# 6809_EXPANDED_V2_SBC.net
KiCad netlist of a schematic drawn in EAGLE
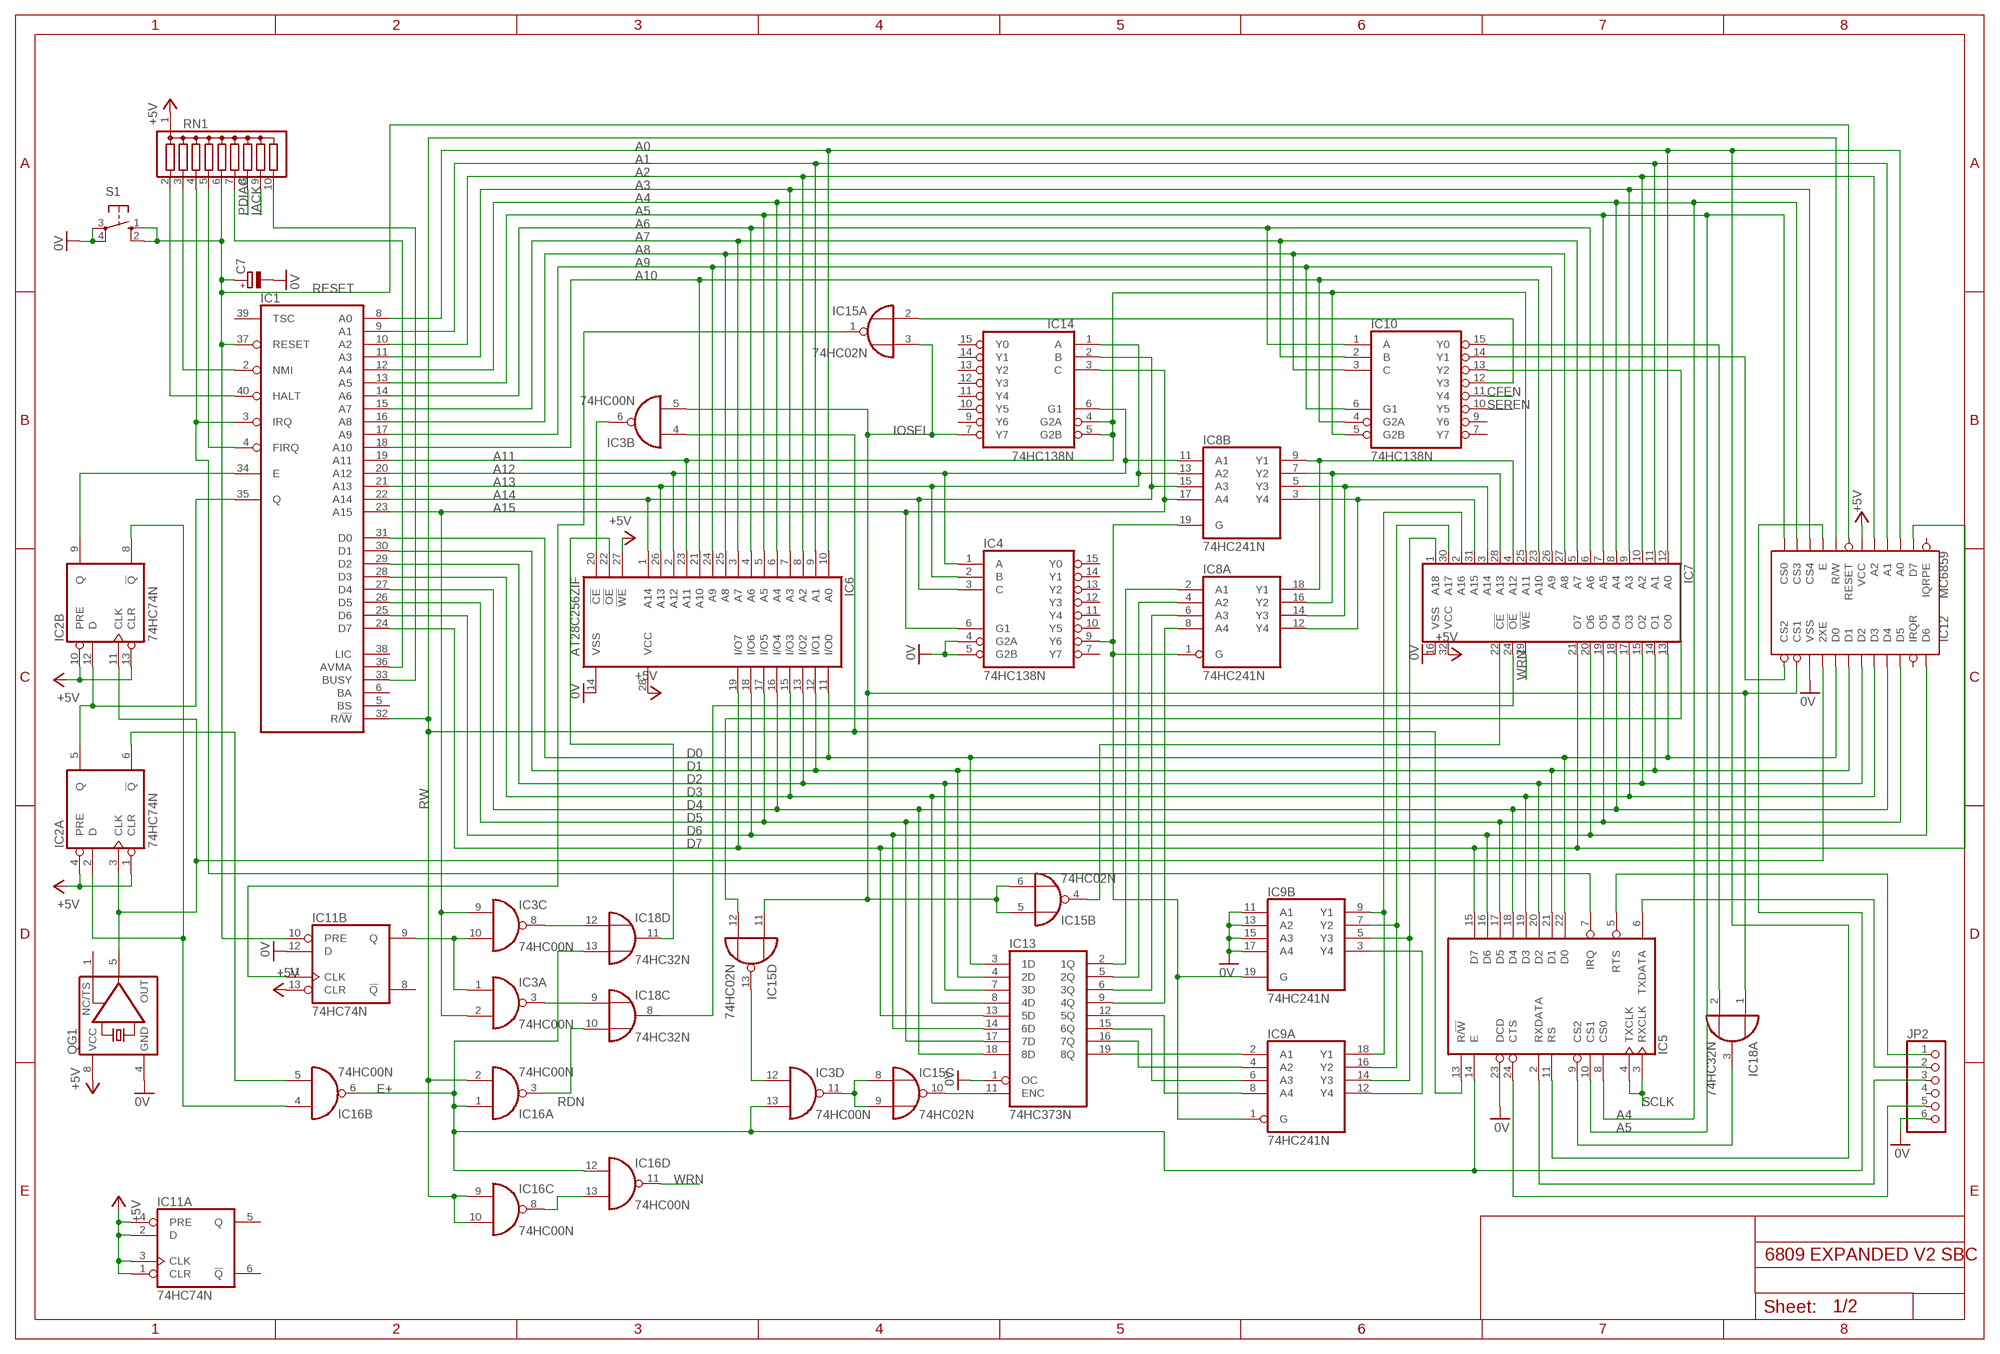
[diagram p0: schematic, sheet 1]
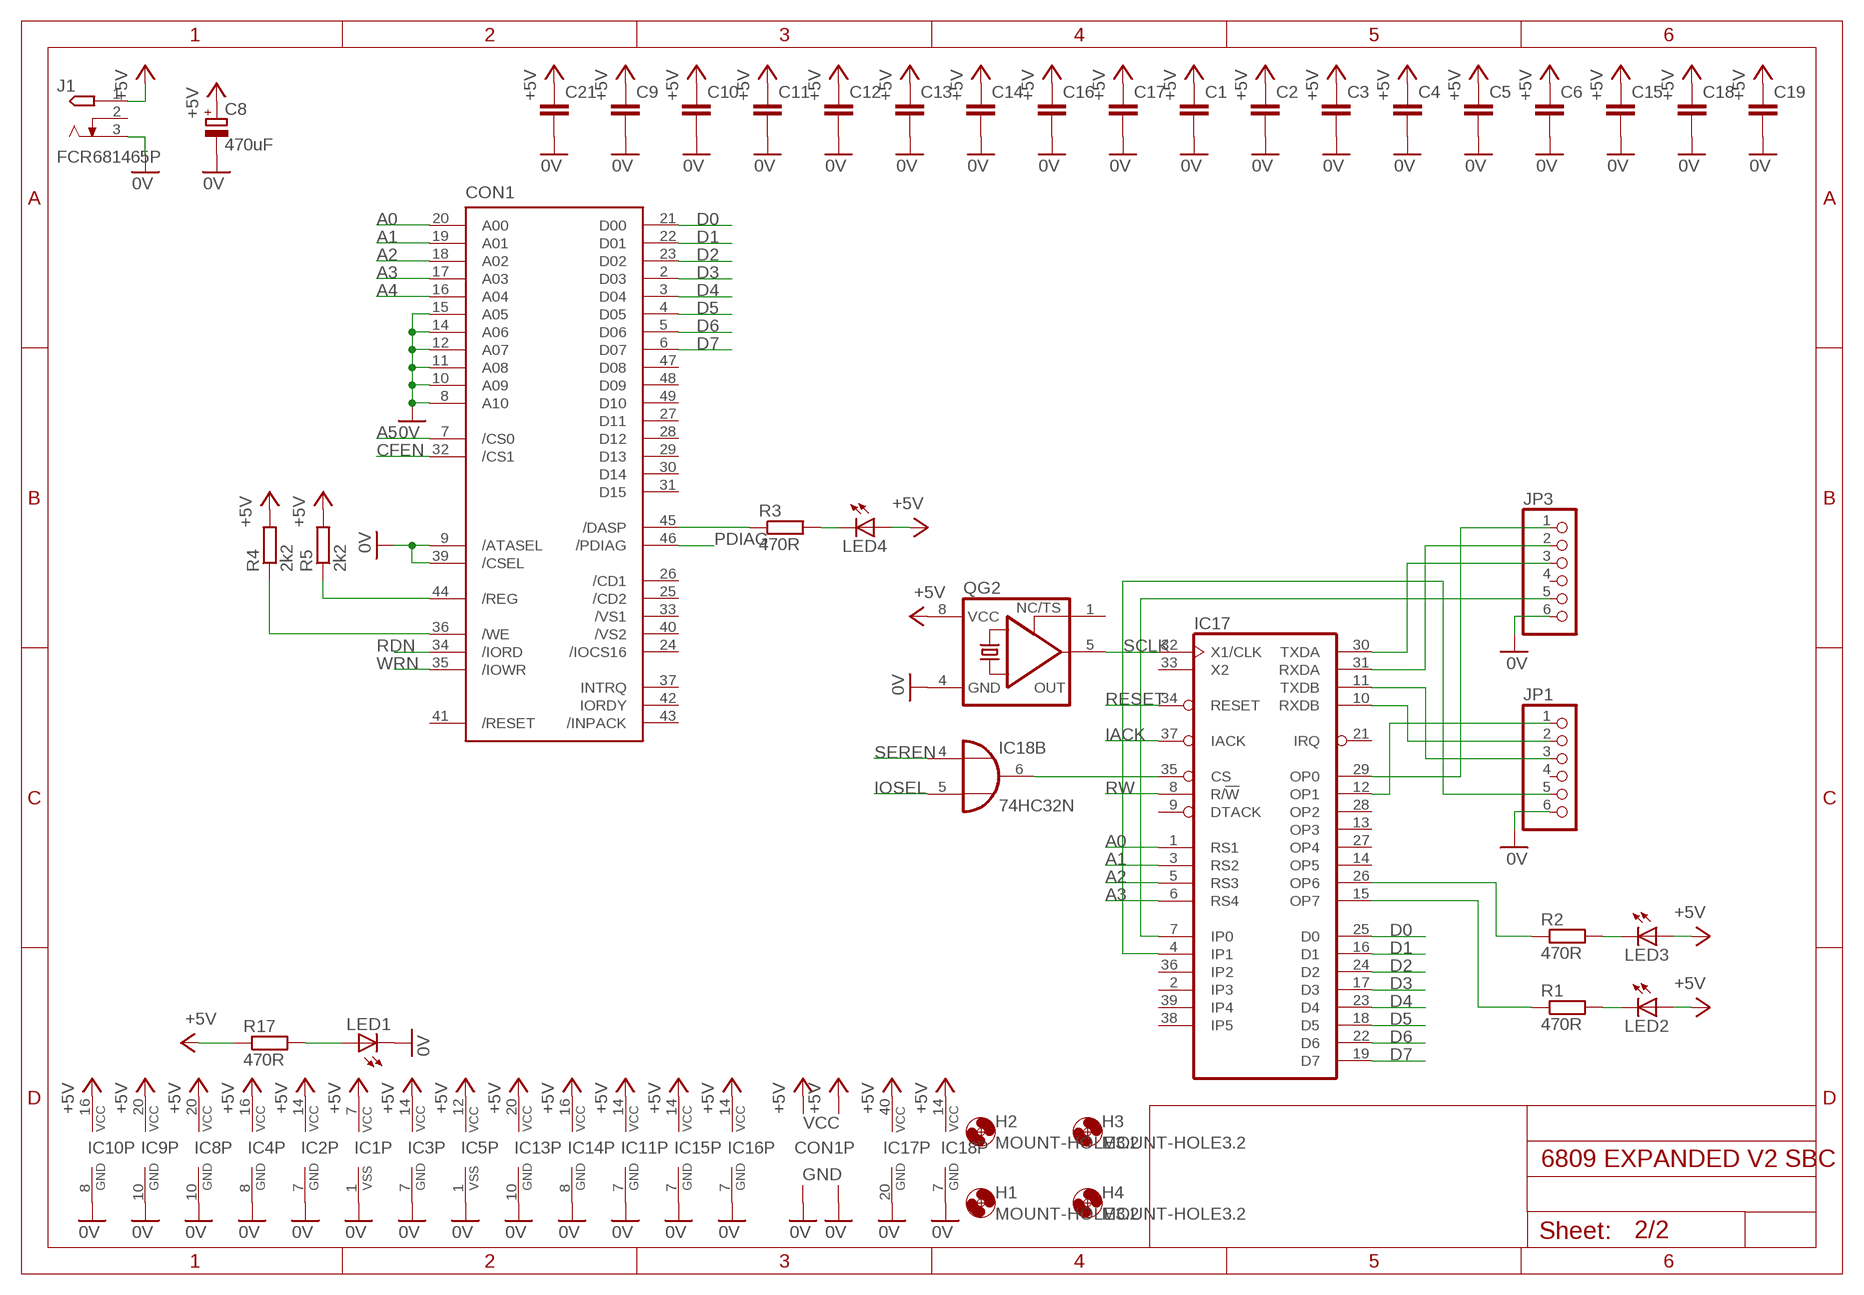
[diagram p1: schematic, sheet 2]

(export (version "E")
  (design (tool "Eeschema 10.0.6"))
  (components
    (comp (ref "C7")
      (value "CPOL-EUE2-5")
      (footprint "eagle-import:E2-5")
      (libsource (lib "eagle-import") (part "CPOL-EUE2-5"))
    )
    (comp (ref "IC1")
      (value "6809E")
      (footprint "eagle-import:DIL40")
      (fields (field (name "MF") "NTE ELECTRONICS") (field (name "MPN") "NTE6809E"))
      (libsource (lib "eagle-import") (part "6809E"))
    )
    (comp (ref "IC2")
      (value "74HC74N")
      (footprint "eagle-import:DIL14")
      (libsource (lib "eagle-import") (part "7474NHC"))
    )
    (comp (ref "IC3")
      (value "74HC00N")
      (footprint "eagle-import:DIL14")
      (libsource (lib "eagle-import") (part "7400NHC"))
    )
    (comp (ref "IC4")
      (value "74HC138N")
      (footprint "eagle-import:DIL16")
      (libsource (lib "eagle-import") (part "74138NHC"))
    )
    (comp (ref "IC5")
      (value "6850")
      (footprint "eagle-import:DIL24")
      (fields (field (name "MF") "NTE ELECTRONICS") (field (name "MPN") "NTE6850"))
      (libsource (lib "eagle-import") (part "6850"))
    )
    (comp (ref "IC6")
      (value "AT28C256ZIF")
      (footprint "eagle-import:228-1277-00-0602J")
      (libsource (lib "eagle-import") (part "AT28C256ZIF"))
    )
    (comp (ref "IC7")
      (value "AS6C4008")
      (footprint "eagle-import:DIL32")
      (libsource (lib "eagle-import") (part "AS6C4008"))
    )
    (comp (ref "IC8")
      (value "74HC241N")
      (footprint "eagle-import:DIL20")
      (libsource (lib "eagle-import") (part "74241NHC"))
    )
    (comp (ref "IC9")
      (value "74HC241N")
      (footprint "eagle-import:DIL20")
      (libsource (lib "eagle-import") (part "74241NHC"))
    )
    (comp (ref "IC10")
      (value "74HC138N")
      (footprint "eagle-import:DIL16")
      (libsource (lib "eagle-import") (part "74138NHC"))
    )
    (comp (ref "IC11")
      (value "74HC74N")
      (footprint "eagle-import:DIL14")
      (libsource (lib "eagle-import") (part "7474NHC"))
    )
    (comp (ref "IC12")
      (value "MC6859")
      (footprint "eagle-import:DIL24-6")
      (libsource (lib "eagle-import") (part "MC6859"))
    )
    (comp (ref "IC13")
      (value "74HC373N")
      (footprint "eagle-import:DIL20")
      (libsource (lib "eagle-import") (part "74373NHC"))
    )
    (comp (ref "IC14")
      (value "74HC138N")
      (footprint "eagle-import:DIL16")
      (libsource (lib "eagle-import") (part "74138NHC"))
    )
    (comp (ref "IC15")
      (value "74HC02N")
      (footprint "eagle-import:DIL14")
      (libsource (lib "eagle-import") (part "7402NHC"))
    )
    (comp (ref "IC16")
      (value "74HC00N")
      (footprint "eagle-import:DIL14")
      (libsource (lib "eagle-import") (part "7400NHC"))
    )
    (comp (ref "IC18")
      (value "74HC32N")
      (footprint "eagle-import:DIL14")
      (libsource (lib "eagle-import") (part "7432NHC"))
    )
    (comp (ref "JP2")
      (value "PINHD-1X6/90")
      (footprint "eagle-import:1X06_90")
      (libsource (lib "eagle-import") (part "PINHD-1X6/90"))
    )
    (comp (ref "QG1")
      (value "XO-8")
      (footprint "eagle-import:DIL08S")
      (libsource (lib "eagle-import") (part "XO-8"))
    )
    (comp (ref "RN1")
      (value "G09R")
      (footprint "eagle-import:SIL10")
      (libsource (lib "eagle-import") (part "G09R"))
    )
    (comp (ref "S1")
      (value "10-XX")
      (footprint "eagle-import:B3F-10XX")
      (fields (field (name "MPN") "B3F-1000"))
      (libsource (lib "eagle-import") (part "10-XX"))
    )
    (comp (ref "C1")
      (value "C-EU025-025X050")
      (footprint "eagle-import:C025-025X050")
      (libsource (lib "eagle-import") (part "C-EU025-025X050"))
    )
    (comp (ref "C2")
      (value "C-EU025-025X050")
      (footprint "eagle-import:C025-025X050")
      (libsource (lib "eagle-import") (part "C-EU025-025X050"))
    )
    (comp (ref "C3")
      (value "C-EU025-025X050")
      (footprint "eagle-import:C025-025X050")
      (libsource (lib "eagle-import") (part "C-EU025-025X050"))
    )
    (comp (ref "C4")
      (value "C-EU025-025X050")
      (footprint "eagle-import:C025-025X050")
      (libsource (lib "eagle-import") (part "C-EU025-025X050"))
    )
    (comp (ref "C5")
      (value "C-EU025-025X050")
      (footprint "eagle-import:C025-025X050")
      (libsource (lib "eagle-import") (part "C-EU025-025X050"))
    )
    (comp (ref "C6")
      (value "C-EU025-025X050")
      (footprint "eagle-import:C025-025X050")
      (libsource (lib "eagle-import") (part "C-EU025-025X050"))
    )
    (comp (ref "C8")
      (value "470uF")
      (footprint "eagle-import:E5-10,5")
      (libsource (lib "eagle-import") (part "CPOL-EUE5-10.5"))
    )
    (comp (ref "C9")
      (value "C-EU025-025X050")
      (footprint "eagle-import:C025-025X050")
      (libsource (lib "eagle-import") (part "C-EU025-025X050"))
    )
    (comp (ref "C10")
      (value "C-EU025-025X050")
      (footprint "eagle-import:C025-025X050")
      (libsource (lib "eagle-import") (part "C-EU025-025X050"))
    )
    (comp (ref "C11")
      (value "C-EU025-025X050")
      (footprint "eagle-import:C025-025X050")
      (libsource (lib "eagle-import") (part "C-EU025-025X050"))
    )
    (comp (ref "C12")
      (value "C-EU025-025X050")
      (footprint "eagle-import:C025-025X050")
      (libsource (lib "eagle-import") (part "C-EU025-025X050"))
    )
    (comp (ref "C13")
      (value "C-EU025-025X050")
      (footprint "eagle-import:C025-025X050")
      (libsource (lib "eagle-import") (part "C-EU025-025X050"))
    )
    (comp (ref "C14")
      (value "C-EU025-025X050")
      (footprint "eagle-import:C025-025X050")
      (libsource (lib "eagle-import") (part "C-EU025-025X050"))
    )
    (comp (ref "C15")
      (value "C-EU025-025X050")
      (footprint "eagle-import:C025-025X050")
      (libsource (lib "eagle-import") (part "C-EU025-025X050"))
    )
    (comp (ref "C16")
      (value "C-EU025-025X050")
      (footprint "eagle-import:C025-025X050")
      (libsource (lib "eagle-import") (part "C-EU025-025X050"))
    )
    (comp (ref "C17")
      (value "C-EU025-025X050")
      (footprint "eagle-import:C025-025X050")
      (libsource (lib "eagle-import") (part "C-EU025-025X050"))
    )
    (comp (ref "C18")
      (value "C-EU025-025X050")
      (footprint "eagle-import:C025-025X050")
      (libsource (lib "eagle-import") (part "C-EU025-025X050"))
    )
    (comp (ref "C19")
      (value "C-EU025-025X050")
      (footprint "eagle-import:C025-025X050")
      (libsource (lib "eagle-import") (part "C-EU025-025X050"))
    )
    (comp (ref "C21")
      (value "C-EU025-025X050")
      (footprint "eagle-import:C025-025X050")
      (libsource (lib "eagle-import") (part "C-EU025-025X050"))
    )
    (comp (ref "CON1")
      (value "CF-CARD-IDE_MODE")
      (footprint "eagle-import:MI20-50PD-SF")
      (libsource (lib "eagle-import") (part "CF-CARD-IDE_MODE"))
    )
    (comp (ref "H1")
      (value "MOUNT-HOLE3.2")
      (footprint "eagle-import:3,2")
      (libsource (lib "eagle-import") (part "MOUNT-HOLE3.2"))
    )
    (comp (ref "H2")
      (value "MOUNT-HOLE3.2")
      (footprint "eagle-import:3,2")
      (libsource (lib "eagle-import") (part "MOUNT-HOLE3.2"))
    )
    (comp (ref "H3")
      (value "MOUNT-HOLE3.2")
      (footprint "eagle-import:3,2")
      (libsource (lib "eagle-import") (part "MOUNT-HOLE3.2"))
    )
    (comp (ref "H4")
      (value "MOUNT-HOLE3.2")
      (footprint "eagle-import:3,2")
      (libsource (lib "eagle-import") (part "MOUNT-HOLE3.2"))
    )
    (comp (ref "IC17")
      (value "MC68681P")
      (footprint "eagle-import:DIL40")
      (libsource (lib "eagle-import") (part "MC68681P"))
    )
    (comp (ref "J1")
      (value "FCR681465P")
      (footprint "eagle-import:FCR681465P")
      (libsource (lib "eagle-import") (part "FCR681465P"))
    )
    (comp (ref "JP1")
      (value "PINHD-1X6/90")
      (footprint "eagle-import:1X06_90")
      (libsource (lib "eagle-import") (part "PINHD-1X6/90"))
    )
    (comp (ref "JP3")
      (value "PINHD-1X6/90")
      (footprint "eagle-import:1X06_90")
      (libsource (lib "eagle-import") (part "PINHD-1X6/90"))
    )
    (comp (ref "LED1")
      (value "LED3MM")
      (footprint "eagle-import:LED3MM")
      (libsource (lib "eagle-import") (part "LED3MM"))
    )
    (comp (ref "LED2")
      (value "LED3MM")
      (footprint "eagle-import:LED3MM")
      (libsource (lib "eagle-import") (part "LED3MM"))
    )
    (comp (ref "LED3")
      (value "LED3MM")
      (footprint "eagle-import:LED3MM")
      (libsource (lib "eagle-import") (part "LED3MM"))
    )
    (comp (ref "LED4")
      (value "LED3MM")
      (footprint "eagle-import:LED3MM")
      (libsource (lib "eagle-import") (part "LED3MM"))
    )
    (comp (ref "QG2")
      (value "XO-8")
      (footprint "eagle-import:DIL08S")
      (libsource (lib "eagle-import") (part "XO-8"))
    )
    (comp (ref "R1")
      (value "470R")
      (footprint "eagle-import:0207_10")
      (libsource (lib "eagle-import") (part "R-EU_0207/10"))
    )
    (comp (ref "R2")
      (value "470R")
      (footprint "eagle-import:0207_10")
      (libsource (lib "eagle-import") (part "R-EU_0207/10"))
    )
    (comp (ref "R3")
      (value "470R")
      (footprint "eagle-import:0207_10")
      (libsource (lib "eagle-import") (part "R-EU_0207/10"))
    )
    (comp (ref "R4")
      (value "2k2")
      (footprint "eagle-import:0207_10")
      (libsource (lib "eagle-import") (part "R-EU_0207/10"))
    )
    (comp (ref "R5")
      (value "2k2")
      (footprint "eagle-import:0207_10")
      (libsource (lib "eagle-import") (part "R-EU_0207/10"))
    )
    (comp (ref "R17")
      (value "470R")
      (footprint "eagle-import:0207_10")
      (libsource (lib "eagle-import") (part "R-EU_0207/10"))
    )
  )
  (nets
    (net (code "1") (name "+5V") (class "Default")
      (node (ref "C1") (pin "1") (pinfunction "1_1") (pintype "passive"))
      (node (ref "C10") (pin "1") (pinfunction "1_1") (pintype "passive"))
      (node (ref "C11") (pin "1") (pinfunction "1_1") (pintype "passive"))
      (node (ref "C12") (pin "1") (pinfunction "1_1") (pintype "passive"))
      (node (ref "C13") (pin "1") (pinfunction "1_1") (pintype "passive"))
      (node (ref "C14") (pin "1") (pinfunction "1_1") (pintype "passive"))
      (node (ref "C15") (pin "1") (pinfunction "1_1") (pintype "passive"))
      (node (ref "C16") (pin "1") (pinfunction "1_1") (pintype "passive"))
      (node (ref "C17") (pin "1") (pinfunction "1_1") (pintype "passive"))
      (node (ref "C18") (pin "1") (pinfunction "1_1") (pintype "passive"))
      (node (ref "C19") (pin "1") (pinfunction "1_1") (pintype "passive"))
      (node (ref "C2") (pin "1") (pinfunction "1_1") (pintype "passive"))
      (node (ref "C21") (pin "1") (pinfunction "1_1") (pintype "passive"))
      (node (ref "C3") (pin "1") (pinfunction "1_1") (pintype "passive"))
      (node (ref "C4") (pin "1") (pinfunction "1_1") (pintype "passive"))
      (node (ref "C5") (pin "1") (pinfunction "1_1") (pintype "passive"))
      (node (ref "C6") (pin "1") (pinfunction "1_1") (pintype "passive"))
      (node (ref "C8") (pin "+") (pinfunction "+_+") (pintype "passive"))
      (node (ref "C9") (pin "1") (pinfunction "1_1") (pintype "passive"))
      (node (ref "CON1") (pin "13") (pinfunction "VCC2_13") (pintype "power_in"))
      (node (ref "CON1") (pin "38") (pinfunction "VCC1_38") (pintype "power_in"))
      (node (ref "IC1") (pin "7") (pinfunction "VCC_7") (pintype "power_in"))
      (node (ref "IC10") (pin "16") (pinfunction "VCC_16") (pintype "power_in"))
      (node (ref "IC11") (pin "1") (pinfunction "CLR_1") (pintype "input"))
      (node (ref "IC11") (pin "13") (pinfunction "CLR_13") (pintype "input"))
      (node (ref "IC11") (pin "14") (pinfunction "VCC_14") (pintype "power_in"))
      (node (ref "IC11") (pin "2") (pinfunction "D_2") (pintype "input"))
      (node (ref "IC11") (pin "3") (pinfunction "CLK_3") (pintype "input"))
      (node (ref "IC11") (pin "4") (pinfunction "PRE_4") (pintype "input"))
      (node (ref "IC12") (pin "6") (pinfunction "VCC_6") (pintype "bidirectional"))
      (node (ref "IC13") (pin "20") (pinfunction "VCC_20") (pintype "power_in"))
      (node (ref "IC14") (pin "16") (pinfunction "VCC_16") (pintype "power_in"))
      (node (ref "IC15") (pin "14") (pinfunction "VCC_14") (pintype "power_in"))
      (node (ref "IC16") (pin "14") (pinfunction "VCC_14") (pintype "power_in"))
      (node (ref "IC17") (pin "40") (pinfunction "VCC_40") (pintype "power_in"))
      (node (ref "IC18") (pin "14") (pinfunction "VCC_14") (pintype "power_in"))
      (node (ref "IC2") (pin "1") (pinfunction "CLR_1") (pintype "input"))
      (node (ref "IC2") (pin "10") (pinfunction "PRE_10") (pintype "input"))
      (node (ref "IC2") (pin "13") (pinfunction "CLR_13") (pintype "input"))
      (node (ref "IC2") (pin "14") (pinfunction "VCC_14") (pintype "power_in"))
      (node (ref "IC2") (pin "4") (pinfunction "PRE_4") (pintype "input"))
      (node (ref "IC3") (pin "14") (pinfunction "VCC_14") (pintype "power_in"))
      (node (ref "IC4") (pin "16") (pinfunction "VCC_16") (pintype "power_in"))
      (node (ref "IC5") (pin "12") (pinfunction "VCC_12") (pintype "power_in"))
      (node (ref "IC6") (pin "27") (pinfunction "~{WE}_27") (pintype "input"))
      (node (ref "IC6") (pin "28") (pinfunction "VCC_28") (pintype "power_in"))
      (node (ref "IC7") (pin "32") (pinfunction "VCC_32") (pintype "tri_state"))
      (node (ref "IC8") (pin "20") (pinfunction "VCC_20") (pintype "power_in"))
      (node (ref "IC9") (pin "20") (pinfunction "VCC_20") (pintype "power_in"))
      (node (ref "J1") (pin "1") (pinfunction "1_1") (pintype "passive"))
      (node (ref "LED2") (pin "A") (pinfunction "A_A") (pintype "passive"))
      (node (ref "LED3") (pin "A") (pinfunction "A_A") (pintype "passive"))
      (node (ref "LED4") (pin "A") (pinfunction "A_A") (pintype "passive"))
      (node (ref "QG1") (pin "8") (pinfunction "VCC_8") (pintype "power_in"))
      (node (ref "QG2") (pin "8") (pinfunction "VCC_8") (pintype "power_in"))
      (node (ref "R17") (pin "1") (pinfunction "1_1") (pintype "passive"))
      (node (ref "R4") (pin "2") (pinfunction "2_2") (pintype "passive"))
      (node (ref "R5") (pin "2") (pinfunction "2_2") (pintype "passive"))
      (node (ref "RN1") (pin "1") (pinfunction "1_1") (pintype "passive"))
    )
    (net (code "2") (name "0V") (class "Default")
      (node (ref "C1") (pin "2") (pinfunction "2_2") (pintype "passive"))
      (node (ref "C10") (pin "2") (pinfunction "2_2") (pintype "passive"))
      (node (ref "C11") (pin "2") (pinfunction "2_2") (pintype "passive"))
      (node (ref "C12") (pin "2") (pinfunction "2_2") (pintype "passive"))
      (node (ref "C13") (pin "2") (pinfunction "2_2") (pintype "passive"))
      (node (ref "C14") (pin "2") (pinfunction "2_2") (pintype "passive"))
      (node (ref "C15") (pin "2") (pinfunction "2_2") (pintype "passive"))
      (node (ref "C16") (pin "2") (pinfunction "2_2") (pintype "passive"))
      (node (ref "C17") (pin "2") (pinfunction "2_2") (pintype "passive"))
      (node (ref "C18") (pin "2") (pinfunction "2_2") (pintype "passive"))
      (node (ref "C19") (pin "2") (pinfunction "2_2") (pintype "passive"))
      (node (ref "C2") (pin "2") (pinfunction "2_2") (pintype "passive"))
      (node (ref "C21") (pin "2") (pinfunction "2_2") (pintype "passive"))
      (node (ref "C3") (pin "2") (pinfunction "2_2") (pintype "passive"))
      (node (ref "C4") (pin "2") (pinfunction "2_2") (pintype "passive"))
      (node (ref "C5") (pin "2") (pinfunction "2_2") (pintype "passive"))
      (node (ref "C6") (pin "2") (pinfunction "2_2") (pintype "passive"))
      (node (ref "C7") (pin "-") (pinfunction "-_-") (pintype "passive"))
      (node (ref "C8") (pin "-") (pinfunction "-_-") (pintype "passive"))
      (node (ref "C9") (pin "2") (pinfunction "2_2") (pintype "passive"))
      (node (ref "CON1") (pin "1") (pinfunction "GND1_1") (pintype "power_in"))
      (node (ref "CON1") (pin "10") (pinfunction "A09_10") (pintype "input"))
      (node (ref "CON1") (pin "11") (pinfunction "A08_11") (pintype "input"))
      (node (ref "CON1") (pin "12") (pinfunction "A07_12") (pintype "input"))
      (node (ref "CON1") (pin "14") (pinfunction "A06_14") (pintype "input"))
      (node (ref "CON1") (pin "15") (pinfunction "A05_15") (pintype "input"))
      (node (ref "CON1") (pin "39") (pinfunction "/CSEL_39") (pintype "input"))
      (node (ref "CON1") (pin "50") (pinfunction "GND2_50") (pintype "power_in"))
      (node (ref "CON1") (pin "8") (pinfunction "A10_8") (pintype "input"))
      (node (ref "CON1") (pin "9") (pinfunction "/ATASEL_9") (pintype "input"))
      (node (ref "IC1") (pin "1") (pinfunction "VSS_1") (pintype "power_in"))
      (node (ref "IC10") (pin "8") (pinfunction "GND_8") (pintype "power_in"))
      (node (ref "IC11") (pin "12") (pinfunction "D_12") (pintype "input"))
      (node (ref "IC11") (pin "7") (pinfunction "GND_7") (pintype "power_in"))
      (node (ref "IC12") (pin "15") (pinfunction "VSS_15") (pintype "bidirectional"))
      (node (ref "IC13") (pin "1") (pinfunction "OC_1") (pintype "input"))
      (node (ref "IC13") (pin "10") (pinfunction "GND_10") (pintype "power_in"))
      (node (ref "IC14") (pin "8") (pinfunction "GND_8") (pintype "power_in"))
      (node (ref "IC15") (pin "7") (pinfunction "GND_7") (pintype "power_in"))
      (node (ref "IC16") (pin "7") (pinfunction "GND_7") (pintype "power_in"))
      (node (ref "IC17") (pin "20") (pinfunction "GND_20") (pintype "power_in"))
      (node (ref "IC18") (pin "7") (pinfunction "GND_7") (pintype "power_in"))
      (node (ref "IC2") (pin "7") (pinfunction "GND_7") (pintype "power_in"))
      (node (ref "IC3") (pin "7") (pinfunction "GND_7") (pintype "power_in"))
      (node (ref "IC4") (pin "4") (pinfunction "G2A_4") (pintype "input"))
      (node (ref "IC4") (pin "5") (pinfunction "G2B_5") (pintype "input"))
      (node (ref "IC4") (pin "8") (pinfunction "GND_8") (pintype "power_in"))
      (node (ref "IC5") (pin "1") (pinfunction "VSS_1") (pintype "power_in"))
      (node (ref "IC5") (pin "23") (pinfunction "DCD_23") (pintype "input"))
      (node (ref "IC6") (pin "14") (pinfunction "VSS_14") (pintype "power_in"))
      (node (ref "IC7") (pin "16") (pinfunction "VSS_16") (pintype "tri_state"))
      (node (ref "IC8") (pin "10") (pinfunction "GND_10") (pintype "power_in"))
      (node (ref "IC9") (pin "10") (pinfunction "GND_10") (pintype "power_in"))
      (node (ref "IC9") (pin "11") (pinfunction "A1_11") (pintype "input"))
      (node (ref "IC9") (pin "13") (pinfunction "A2_13") (pintype "input"))
      (node (ref "IC9") (pin "15") (pinfunction "A3_15") (pintype "input"))
      (node (ref "IC9") (pin "17") (pinfunction "A4_17") (pintype "input"))
      (node (ref "J1") (pin "3") (pinfunction "3_3") (pintype "passive"))
      (node (ref "JP1") (pin "6") (pinfunction "6_6") (pintype "passive"))
      (node (ref "JP2") (pin "6") (pinfunction "6_6") (pintype "passive"))
      (node (ref "JP3") (pin "6") (pinfunction "6_6") (pintype "passive"))
      (node (ref "LED1") (pin "K") (pinfunction "C_K") (pintype "passive"))
      (node (ref "QG1") (pin "4") (pinfunction "GND_4") (pintype "power_in"))
      (node (ref "QG2") (pin "4") (pinfunction "GND_4") (pintype "power_in"))
      (node (ref "S1") (pin "3") (pinfunction "P_3") (pintype "passive"))
      (node (ref "S1") (pin "4") (pinfunction "P1_4") (pintype "passive"))
    )
    (net (code "3") (name "A0") (class "Default")
      (node (ref "CON1") (pin "20") (pinfunction "A00_20") (pintype "input"))
      (node (ref "IC1") (pin "8") (pinfunction "A0_8") (pintype "tri_state"))
      (node (ref "IC12") (pin "3") (pinfunction "A0_3") (pintype "bidirectional"))
      (node (ref "IC17") (pin "1") (pinfunction "RS1_1") (pintype "input"))
      (node (ref "IC5") (pin "11") (pinfunction "RS_11") (pintype "input"))
      (node (ref "IC6") (pin "10") (pinfunction "A0_10") (pintype "input"))
      (node (ref "IC7") (pin "12") (pinfunction "A0_12") (pintype "input"))
    )
    (net (code "4") (name "A1") (class "Default")
      (node (ref "CON1") (pin "19") (pinfunction "A01_19") (pintype "input"))
      (node (ref "IC1") (pin "9") (pinfunction "A1_9") (pintype "tri_state"))
      (node (ref "IC12") (pin "4") (pinfunction "A1_4") (pintype "bidirectional"))
      (node (ref "IC17") (pin "3") (pinfunction "RS2_3") (pintype "input"))
      (node (ref "IC6") (pin "9") (pinfunction "A1_9") (pintype "input"))
      (node (ref "IC7") (pin "11") (pinfunction "A1_11") (pintype "input"))
    )
    (net (code "5") (name "A2") (class "Default")
      (node (ref "CON1") (pin "18") (pinfunction "A02_18") (pintype "input"))
      (node (ref "IC1") (pin "10") (pinfunction "A2_10") (pintype "tri_state"))
      (node (ref "IC12") (pin "5") (pinfunction "A2_5") (pintype "bidirectional"))
      (node (ref "IC17") (pin "5") (pinfunction "RS3_5") (pintype "input"))
      (node (ref "IC6") (pin "8") (pinfunction "A2_8") (pintype "input"))
      (node (ref "IC7") (pin "10") (pinfunction "A2_10") (pintype "input"))
    )
    (net (code "6") (name "A3") (class "Default")
      (node (ref "CON1") (pin "17") (pinfunction "A03_17") (pintype "input"))
      (node (ref "IC1") (pin "11") (pinfunction "A3_11") (pintype "tri_state"))
      (node (ref "IC12") (pin "10") (pinfunction "CS4_10") (pintype "bidirectional"))
      (node (ref "IC17") (pin "6") (pinfunction "RS4_6") (pintype "input"))
      (node (ref "IC6") (pin "7") (pinfunction "A3_7") (pintype "input"))
      (node (ref "IC7") (pin "9") (pinfunction "A3_9") (pintype "input"))
    )
    (net (code "7") (name "A4") (class "Default")
      (node (ref "CON1") (pin "16") (pinfunction "A04_16") (pintype "input"))
      (node (ref "IC1") (pin "12") (pinfunction "A4_12") (pintype "tri_state"))
      (node (ref "IC12") (pin "11") (pinfunction "CS3_11") (pintype "bidirectional"))
      (node (ref "IC5") (pin "8") (pinfunction "CS0_8") (pintype "input"))
      (node (ref "IC6") (pin "6") (pinfunction "A4_6") (pintype "input"))
      (node (ref "IC7") (pin "8") (pinfunction "A4_8") (pintype "input"))
    )
    (net (code "8") (name "A5") (class "Default")
      (node (ref "CON1") (pin "7") (pinfunction "/CS0_7") (pintype "input"))
      (node (ref "IC1") (pin "13") (pinfunction "A5_13") (pintype "tri_state"))
      (node (ref "IC12") (pin "12") (pinfunction "CS0_12") (pintype "bidirectional"))
      (node (ref "IC5") (pin "10") (pinfunction "CS1_10") (pintype "input"))
      (node (ref "IC6") (pin "5") (pinfunction "A5_5") (pintype "input"))
      (node (ref "IC7") (pin "7") (pinfunction "A5_7") (pintype "input"))
    )
    (net (code "9") (name "A6") (class "Default")
      (node (ref "IC1") (pin "14") (pinfunction "A6_14") (pintype "tri_state"))
      (node (ref "IC10") (pin "1") (pinfunction "A_1") (pintype "input"))
      (node (ref "IC6") (pin "4") (pinfunction "A6_4") (pintype "input"))
      (node (ref "IC7") (pin "6") (pinfunction "A6_6") (pintype "input"))
    )
    (net (code "10") (name "A7") (class "Default")
      (node (ref "IC1") (pin "15") (pinfunction "A7_15") (pintype "tri_state"))
      (node (ref "IC10") (pin "2") (pinfunction "B_2") (pintype "input"))
      (node (ref "IC6") (pin "3") (pinfunction "A7_3") (pintype "input"))
      (node (ref "IC7") (pin "5") (pinfunction "A7_5") (pintype "input"))
    )
    (net (code "11") (name "A8") (class "Default")
      (node (ref "IC1") (pin "16") (pinfunction "A8_16") (pintype "tri_state"))
      (node (ref "IC10") (pin "3") (pinfunction "C_3") (pintype "input"))
      (node (ref "IC6") (pin "25") (pinfunction "A8_25") (pintype "input"))
      (node (ref "IC7") (pin "27") (pinfunction "A8_27") (pintype "input"))
    )
    (net (code "12") (name "A9") (class "Default")
      (node (ref "IC1") (pin "17") (pinfunction "A9_17") (pintype "tri_state"))
      (node (ref "IC10") (pin "6") (pinfunction "G1_6") (pintype "input"))
      (node (ref "IC6") (pin "24") (pinfunction "A9_24") (pintype "input"))
      (node (ref "IC7") (pin "26") (pinfunction "A9_26") (pintype "input"))
    )
    (net (code "13") (name "A10") (class "Default")
      (node (ref "IC1") (pin "18") (pinfunction "A10_18") (pintype "tri_state"))
      (node (ref "IC10") (pin "4") (pinfunction "G2A_4") (pintype "input"))
      (node (ref "IC6") (pin "21") (pinfunction "A10_21") (pintype "input"))
      (node (ref "IC7") (pin "23") (pinfunction "A10_23") (pintype "input"))
    )
    (net (code "14") (name "A11") (class "Default")
      (node (ref "IC1") (pin "19") (pinfunction "A11_19") (pintype "tri_state"))
      (node (ref "IC10") (pin "5") (pinfunction "G2B_5") (pintype "input"))
      (node (ref "IC14") (pin "4") (pinfunction "G2A_4") (pintype "input"))
      (node (ref "IC14") (pin "5") (pinfunction "G2B_5") (pintype "input"))
      (node (ref "IC6") (pin "23") (pinfunction "A11_23") (pintype "input"))
      (node (ref "IC7") (pin "25") (pinfunction "A11_25") (pintype "input"))
    )
    (net (code "15") (name "A12") (class "Default")
      (node (ref "IC1") (pin "20") (pinfunction "A12_20") (pintype "tri_state"))
      (node (ref "IC14") (pin "6") (pinfunction "G1_6") (pintype "input"))
      (node (ref "IC4") (pin "1") (pinfunction "A_1") (pintype "input"))
      (node (ref "IC6") (pin "2") (pinfunction "A12_2") (pintype "input"))
      (node (ref "IC8") (pin "11") (pinfunction "A1_11") (pintype "input"))
    )
    (net (code "16") (name "A13") (class "Default")
      (node (ref "IC1") (pin "21") (pinfunction "A13_21") (pintype "tri_state"))
      (node (ref "IC14") (pin "1") (pinfunction "A_1") (pintype "input"))
      (node (ref "IC4") (pin "2") (pinfunction "B_2") (pintype "input"))
      (node (ref "IC6") (pin "26") (pinfunction "A13_26") (pintype "input"))
      (node (ref "IC8") (pin "13") (pinfunction "A2_13") (pintype "input"))
    )
    (net (code "17") (name "A14") (class "Default")
      (node (ref "IC1") (pin "22") (pinfunction "A14_22") (pintype "tri_state"))
      (node (ref "IC14") (pin "2") (pinfunction "B_2") (pintype "input"))
      (node (ref "IC4") (pin "3") (pinfunction "C_3") (pintype "input"))
      (node (ref "IC6") (pin "1") (pinfunction "A14_1") (pintype "input"))
      (node (ref "IC8") (pin "15") (pinfunction "A3_15") (pintype "input"))
    )
    (net (code "18") (name "A15") (class "Default")
      (node (ref "IC1") (pin "23") (pinfunction "A15_23") (pintype "tri_state"))
      (node (ref "IC14") (pin "3") (pinfunction "C_3") (pintype "input"))
      (node (ref "IC3") (pin "2") (pinfunction "I1_2") (pintype "input"))
      (node (ref "IC3") (pin "9") (pinfunction "I0_9") (pintype "input"))
      (node (ref "IC4") (pin "6") (pinfunction "G1_6") (pintype "input"))
      (node (ref "IC8") (pin "17") (pinfunction "A4_17") (pintype "input"))
    )
    (net (code "19") (name "CFEN") (class "Default")
      (node (ref "CON1") (pin "32") (pinfunction "/CS1_32") (pintype "input"))
      (node (ref "IC10") (pin "11") (pinfunction "Y4_11") (pintype "output"))
    )
    (net (code "20") (name "D0") (class "Default")
      (node (ref "CON1") (pin "21") (pinfunction "D00_21") (pintype "bidirectional"))
      (node (ref "IC1") (pin "31") (pinfunction "D0_31") (pintype "bidirectional"))
      (node (ref "IC12") (pin "17") (pinfunction "D0_17") (pintype "bidirectional"))
      (node (ref "IC13") (pin "3") (pinfunction "1D_3") (pintype "input"))
      (node (ref "IC17") (pin "25") (pinfunction "D0_25") (pintype "bidirectional"))
      (node (ref "IC5") (pin "22") (pinfunction "D0_22") (pintype "bidirectional"))
      (node (ref "IC6") (pin "11") (pinfunction "I/O0_11") (pintype "tri_state"))
      (node (ref "IC7") (pin "13") (pinfunction "O0_13") (pintype "tri_state"))
    )
    (net (code "21") (name "D1") (class "Default")
      (node (ref "CON1") (pin "22") (pinfunction "D01_22") (pintype "bidirectional"))
      (node (ref "IC1") (pin "30") (pinfunction "D1_30") (pintype "bidirectional"))
      (node (ref "IC12") (pin "18") (pinfunction "D1_18") (pintype "bidirectional"))
      (node (ref "IC13") (pin "4") (pinfunction "2D_4") (pintype "input"))
      (node (ref "IC17") (pin "16") (pinfunction "D1_16") (pintype "bidirectional"))
      (node (ref "IC5") (pin "21") (pinfunction "D1_21") (pintype "bidirectional"))
      (node (ref "IC6") (pin "12") (pinfunction "I/O1_12") (pintype "tri_state"))
      (node (ref "IC7") (pin "14") (pinfunction "O1_14") (pintype "tri_state"))
    )
    (net (code "22") (name "D2") (class "Default")
      (node (ref "CON1") (pin "23") (pinfunction "D02_23") (pintype "bidirectional"))
      (node (ref "IC1") (pin "29") (pinfunction "D2_29") (pintype "bidirectional"))
      (node (ref "IC12") (pin "19") (pinfunction "D2_19") (pintype "bidirectional"))
      (node (ref "IC13") (pin "7") (pinfunction "3D_7") (pintype "input"))
      (node (ref "IC17") (pin "24") (pinfunction "D2_24") (pintype "bidirectional"))
      (node (ref "IC5") (pin "20") (pinfunction "D2_20") (pintype "bidirectional"))
      (node (ref "IC6") (pin "13") (pinfunction "I/O2_13") (pintype "tri_state"))
      (node (ref "IC7") (pin "15") (pinfunction "O2_15") (pintype "tri_state"))
    )
    (net (code "23") (name "D3") (class "Default")
      (node (ref "CON1") (pin "2") (pinfunction "D03_2") (pintype "bidirectional"))
      (node (ref "IC1") (pin "28") (pinfunction "D3_28") (pintype "bidirectional"))
      (node (ref "IC12") (pin "20") (pinfunction "D3_20") (pintype "bidirectional"))
      (node (ref "IC13") (pin "8") (pinfunction "4D_8") (pintype "input"))
      (node (ref "IC17") (pin "17") (pinfunction "D3_17") (pintype "bidirectional"))
      (node (ref "IC5") (pin "19") (pinfunction "D3_19") (pintype "bidirectional"))
      (node (ref "IC6") (pin "15") (pinfunction "I/O3_15") (pintype "tri_state"))
      (node (ref "IC7") (pin "17") (pinfunction "O3_17") (pintype "tri_state"))
    )
    (net (code "24") (name "D4") (class "Default")
      (node (ref "CON1") (pin "3") (pinfunction "D04_3") (pintype "bidirectional"))
      (node (ref "IC1") (pin "27") (pinfunction "D4_27") (pintype "bidirectional"))
      (node (ref "IC12") (pin "21") (pinfunction "D4_21") (pintype "bidirectional"))
      (node (ref "IC13") (pin "18") (pinfunction "8D_18") (pintype "input"))
      (node (ref "IC17") (pin "23") (pinfunction "D4_23") (pintype "bidirectional"))
      (node (ref "IC5") (pin "18") (pinfunction "D4_18") (pintype "bidirectional"))
      (node (ref "IC6") (pin "16") (pinfunction "I/O4_16") (pintype "tri_state"))
      (node (ref "IC7") (pin "18") (pinfunction "O4_18") (pintype "tri_state"))
    )
    (net (code "25") (name "D5") (class "Default")
      (node (ref "CON1") (pin "4") (pinfunction "D05_4") (pintype "bidirectional"))
      (node (ref "IC1") (pin "26") (pinfunction "D5_26") (pintype "bidirectional"))
      (node (ref "IC12") (pin "22") (pinfunction "D5_22") (pintype "bidirectional"))
      (node (ref "IC13") (pin "17") (pinfunction "7D_17") (pintype "input"))
      (node (ref "IC17") (pin "18") (pinfunction "D5_18") (pintype "bidirectional"))
      (node (ref "IC5") (pin "17") (pinfunction "D5_17") (pintype "bidirectional"))
      (node (ref "IC6") (pin "17") (pinfunction "I/O5_17") (pintype "tri_state"))
      (node (ref "IC7") (pin "19") (pinfunction "O5_19") (pintype "tri_state"))
    )
    (net (code "26") (name "D6") (class "Default")
      (node (ref "CON1") (pin "5") (pinfunction "D06_5") (pintype "bidirectional"))
      (node (ref "IC1") (pin "25") (pinfunction "D6_25") (pintype "bidirectional"))
      (node (ref "IC12") (pin "24") (pinfunction "D6_24") (pintype "bidirectional"))
      (node (ref "IC13") (pin "14") (pinfunction "6D_14") (pintype "input"))
      (node (ref "IC17") (pin "22") (pinfunction "D6_22") (pintype "bidirectional"))
      (node (ref "IC5") (pin "16") (pinfunction "D6_16") (pintype "bidirectional"))
      (node (ref "IC6") (pin "18") (pinfunction "I/O6_18") (pintype "tri_state"))
      (node (ref "IC7") (pin "20") (pinfunction "O6_20") (pintype "tri_state"))
    )
    (net (code "27") (name "D7") (class "Default")
      (node (ref "CON1") (pin "6") (pinfunction "D07_6") (pintype "bidirectional"))
      (node (ref "IC1") (pin "24") (pinfunction "D7_24") (pintype "bidirectional"))
      (node (ref "IC12") (pin "2") (pinfunction "D7_2") (pintype "bidirectional"))
      (node (ref "IC13") (pin "13") (pinfunction "5D_13") (pintype "input"))
      (node (ref "IC17") (pin "19") (pinfunction "D7_19") (pintype "bidirectional"))
      (node (ref "IC5") (pin "15") (pinfunction "D7_15") (pintype "bidirectional"))
      (node (ref "IC6") (pin "19") (pinfunction "I/O7_19") (pintype "tri_state"))
      (node (ref "IC7") (pin "21") (pinfunction "O7_21") (pintype "tri_state"))
    )
    (net (code "28") (name "E+") (class "Default")
      (node (ref "IC12") (pin "9") (pinfunction "E_9") (pintype "bidirectional"))
      (node (ref "IC16") (pin "1") (pinfunction "I0_1") (pintype "input"))
      (node (ref "IC16") (pin "12") (pinfunction "I0_12") (pintype "input"))
      (node (ref "IC16") (pin "6") (pinfunction "O_6") (pintype "output"))
      (node (ref "IC18") (pin "13") (pinfunction "I1_13") (pintype "input"))
      (node (ref "IC3") (pin "13") (pinfunction "I1_13") (pintype "input"))
      (node (ref "IC5") (pin "14") (pinfunction "E_14") (pintype "input"))
    )
    (net (code "29") (name "IACK") (class "Default")
      (node (ref "IC17") (pin "37") (pinfunction "IACK_37") (pintype "input"))
      (node (ref "RN1") (pin "9") (pinfunction "9_9") (pintype "passive"))
    )
    (net (code "30") (name "IOSEL") (class "Default")
      (node (ref "IC12") (pin "14") (pinfunction "CS1_14") (pintype "bidirectional"))
      (node (ref "IC14") (pin "7") (pinfunction "Y7_7") (pintype "output"))
      (node (ref "IC15") (pin "11") (pinfunction "I0_11") (pintype "input"))
      (node (ref "IC15") (pin "3") (pinfunction "I1_3") (pintype "input"))
      (node (ref "IC15") (pin "5") (pinfunction "I0_5") (pintype "input"))
      (node (ref "IC15") (pin "6") (pinfunction "I1_6") (pintype "input"))
      (node (ref "IC18") (pin "1") (pinfunction "I0_1") (pintype "input"))
      (node (ref "IC18") (pin "5") (pinfunction "I1_5") (pintype "input"))
      (node (ref "IC3") (pin "5") (pinfunction "I1_5") (pintype "input"))
    )
    (net (code "31") (name "Net-(CON1A-{slash}DASP)") (class "Default")
      (node (ref "CON1") (pin "45") (pinfunction "/DASP_45") (pintype "bidirectional"))
      (node (ref "R3") (pin "1") (pinfunction "1_1") (pintype "passive"))
    )
    (net (code "32") (name "Net-(CON1A-{slash}REG)") (class "Default")
      (node (ref "CON1") (pin "44") (pinfunction "/REG_44") (pintype "input"))
      (node (ref "R5") (pin "1") (pinfunction "1_1") (pintype "passive"))
    )
    (net (code "33") (name "Net-(CON1A-{slash}WE)") (class "Default")
      (node (ref "CON1") (pin "36") (pinfunction "/WE_36") (pintype "input"))
      (node (ref "R4") (pin "1") (pinfunction "1_1") (pintype "passive"))
    )
    (net (code "34") (name "Net-(IC1A-AVMA)") (class "Default")
      (node (ref "IC1") (pin "36") (pinfunction "AVMA_36") (pintype "output"))
      (node (ref "RN1") (pin "7") (pinfunction "7_7") (pintype "passive"))
    )
    (net (code "35") (name "Net-(IC1A-BUSY)") (class "Default")
      (node (ref "IC1") (pin "33") (pinfunction "BUSY_33") (pintype "output"))
      (node (ref "RN1") (pin "10") (pinfunction "10_10") (pintype "passive"))
    )
    (net (code "36") (name "Net-(IC1A-E)") (class "Default")
      (node (ref "IC1") (pin "34") (pinfunction "E_34") (pintype "input"))
      (node (ref "IC2") (pin "9") (pinfunction "Q_9") (pintype "output"))
    )
    (net (code "37") (name "Net-(IC1A-FIRQ)") (class "Default")
      (node (ref "IC1") (pin "4") (pinfunction "FIRQ_4") (pintype "input"))
      (node (ref "RN1") (pin "5") (pinfunction "5_5") (pintype "passive"))
    )
    (net (code "38") (name "Net-(IC1A-HALT)") (class "Default")
      (node (ref "IC1") (pin "40") (pinfunction "HALT_40") (pintype "input"))
      (node (ref "RN1") (pin "2") (pinfunction "2_2") (pintype "passive"))
    )
    (net (code "39") (name "Net-(IC1A-IRQ)") (class "Default")
      (node (ref "IC1") (pin "3") (pinfunction "IRQ_3") (pintype "input"))
      (node (ref "IC5") (pin "7") (pinfunction "IRQ_7") (pintype "output"))
      (node (ref "RN1") (pin "4") (pinfunction "4_4") (pintype "passive"))
    )
    (net (code "40") (name "Net-(IC1A-NMI)") (class "Default")
      (node (ref "IC1") (pin "2") (pinfunction "NMI_2") (pintype "input"))
      (node (ref "RN1") (pin "3") (pinfunction "3_3") (pintype "passive"))
    )
    (net (code "41") (name "Net-(IC1A-Q)") (class "Default")
      (node (ref "IC1") (pin "35") (pinfunction "Q_35") (pintype "input"))
      (node (ref "IC2") (pin "12") (pinfunction "D_12") (pintype "input"))
      (node (ref "IC2") (pin "5") (pinfunction "Q_5") (pintype "output"))
    )
    (net (code "42") (name "Net-(IC3B-O)") (class "Default")
      (node (ref "IC3") (pin "6") (pinfunction "O_6") (pintype "output"))
      (node (ref "IC6") (pin "20") (pinfunction "~{CE}_20") (pintype "input"))
    )
    (net (code "43") (name "Net-(IC4A-Y6)") (class "Default")
      (node (ref "IC4") (pin "9") (pinfunction "Y6_9") (pintype "output"))
      (node (ref "IC8") (pin "1") (pinfunction "G_1") (pintype "input"))
      (node (ref "IC8") (pin "19") (pinfunction "G_19") (pintype "input"))
      (node (ref "IC9") (pin "1") (pinfunction "G_1") (pintype "input"))
      (node (ref "IC9") (pin "19") (pinfunction "G_19") (pintype "input"))
    )
    (net (code "44") (name "Net-(IC5A-CTS)") (class "Default")
      (node (ref "IC5") (pin "24") (pinfunction "CTS_24") (pintype "input"))
      (node (ref "JP2") (pin "5") (pinfunction "5_5") (pintype "passive"))
    )
    (net (code "45") (name "Net-(IC5A-RTS)") (class "Default")
      (node (ref "IC5") (pin "5") (pinfunction "RTS_5") (pintype "output"))
      (node (ref "JP2") (pin "1") (pinfunction "1_1") (pintype "passive"))
    )
    (net (code "46") (name "Net-(IC5A-RXDATA)") (class "Default")
      (node (ref "IC5") (pin "2") (pinfunction "RXDATA_2") (pintype "input"))
      (node (ref "JP2") (pin "3") (pinfunction "3_3") (pintype "passive"))
    )
    (net (code "47") (name "Net-(IC5A-TXDATA)") (class "Default")
      (node (ref "IC5") (pin "6") (pinfunction "TXDATA_6") (pintype "output"))
      (node (ref "JP2") (pin "2") (pinfunction "2_2") (pintype "passive"))
    )
    (net (code "48") (name "Net-(IC7-A12)") (class "Default")
      (node (ref "IC7") (pin "4") (pinfunction "A12_4") (pintype "input"))
      (node (ref "IC8") (pin "18") (pinfunction "Y1_18") (pintype "tri_state"))
      (node (ref "IC8") (pin "9") (pinfunction "Y1_9") (pintype "tri_state"))
    )
    (net (code "49") (name "Net-(IC7-A13)") (class "Default")
      (node (ref "IC7") (pin "28") (pinfunction "A13_28") (pintype "input"))
      (node (ref "IC8") (pin "16") (pinfunction "Y2_16") (pintype "tri_state"))
      (node (ref "IC8") (pin "7") (pinfunction "Y2_7") (pintype "tri_state"))
    )
    (net (code "50") (name "Net-(IC7-A14)") (class "Default")
      (node (ref "IC7") (pin "3") (pinfunction "A14_3") (pintype "input"))
      (node (ref "IC8") (pin "14") (pinfunction "Y3_14") (pintype "tri_state"))
      (node (ref "IC8") (pin "5") (pinfunction "Y3_5") (pintype "tri_state"))
    )
    (net (code "51") (name "Net-(IC7-A15)") (class "Default")
      (node (ref "IC7") (pin "31") (pinfunction "A15_31") (pintype "input"))
      (node (ref "IC8") (pin "12") (pinfunction "Y4_12") (pintype "tri_state"))
      (node (ref "IC8") (pin "3") (pinfunction "Y4_3") (pintype "tri_state"))
    )
    (net (code "52") (name "Net-(IC7-A16)") (class "Default")
      (node (ref "IC7") (pin "2") (pinfunction "A16_2") (pintype "input"))
      (node (ref "IC9") (pin "18") (pinfunction "Y1_18") (pintype "tri_state"))
      (node (ref "IC9") (pin "9") (pinfunction "Y1_9") (pintype "tri_state"))
    )
    (net (code "53") (name "Net-(IC7-A17)") (class "Default")
      (node (ref "IC7") (pin "30") (pinfunction "A17_30") (pintype "input"))
      (node (ref "IC9") (pin "16") (pinfunction "Y2_16") (pintype "tri_state"))
      (node (ref "IC9") (pin "7") (pinfunction "Y2_7") (pintype "tri_state"))
    )
    (net (code "54") (name "Net-(IC7-A18)") (class "Default")
      (node (ref "IC7") (pin "1") (pinfunction "A18_1") (pintype "input"))
      (node (ref "IC9") (pin "14") (pinfunction "Y3_14") (pintype "tri_state"))
      (node (ref "IC9") (pin "5") (pinfunction "Y3_5") (pintype "tri_state"))
    )
    (net (code "55") (name "Net-(IC9A-Y4)") (class "Default")
      (node (ref "IC9") (pin "12") (pinfunction "Y4_12") (pintype "tri_state"))
      (node (ref "IC9") (pin "3") (pinfunction "Y4_3") (pintype "tri_state"))
    )
    (net (code "56") (name "Net-(IC10A-Y0)") (class "Default")
      (node (ref "IC10") (pin "15") (pinfunction "Y0_15") (pintype "output"))
      (node (ref "IC18") (pin "2") (pinfunction "I1_2") (pintype "input"))
    )
    (net (code "57") (name "Net-(IC10A-Y1)") (class "Default")
      (node (ref "IC10") (pin "14") (pinfunction "Y1_14") (pintype "output"))
      (node (ref "IC12") (pin "13") (pinfunction "CS2_13") (pintype "bidirectional"))
    )
    (net (code "58") (name "Net-(IC10A-Y2)") (class "Default")
      (node (ref "IC10") (pin "13") (pinfunction "Y2_13") (pintype "output"))
      (node (ref "IC15") (pin "12") (pinfunction "I1_12") (pintype "input"))
    )
    (net (code "59") (name "Net-(IC10A-Y3)") (class "Default")
      (node (ref "IC10") (pin "12") (pinfunction "Y3_12") (pintype "output"))
      (node (ref "IC15") (pin "2") (pinfunction "I0_2") (pintype "input"))
    )
    (net (code "60") (name "Net-(IC11B-CLK)") (class "Default")
      (node (ref "IC11") (pin "11") (pinfunction "CLK_11") (pintype "input"))
      (node (ref "IC15") (pin "1") (pinfunction "O_1") (pintype "output"))
    )
    (net (code "61") (name "Net-(IC11B-Q)") (class "Default")
      (node (ref "IC11") (pin "9") (pinfunction "Q_9") (pintype "output"))
      (node (ref "IC3") (pin "1") (pinfunction "I0_1") (pintype "input"))
      (node (ref "IC3") (pin "10") (pinfunction "I1_10") (pintype "input"))
    )
    (net (code "62") (name "Net-(IC12-2XE)") (class "Default")
      (node (ref "IC12") (pin "16") (pinfunction "2XE_16") (pintype "bidirectional"))
      (node (ref "IC2") (pin "11") (pinfunction "CLK_11") (pintype "input"))
      (node (ref "IC2") (pin "3") (pinfunction "CLK_3") (pintype "input"))
      (node (ref "QG1") (pin "5") (pinfunction "OUT_5") (pintype "output"))
    )
    (net (code "63") (name "Net-(IC13A-1Q)") (class "Default")
      (node (ref "IC13") (pin "2") (pinfunction "1Q_2") (pintype "tri_state"))
      (node (ref "IC8") (pin "2") (pinfunction "A1_2") (pintype "input"))
    )
    (net (code "64") (name "Net-(IC13A-2Q)") (class "Default")
      (node (ref "IC13") (pin "5") (pinfunction "2Q_5") (pintype "tri_state"))
      (node (ref "IC8") (pin "4") (pinfunction "A2_4") (pintype "input"))
    )
    (net (code "65") (name "Net-(IC13A-3Q)") (class "Default")
      (node (ref "IC13") (pin "6") (pinfunction "3Q_6") (pintype "tri_state"))
      (node (ref "IC8") (pin "6") (pinfunction "A3_6") (pintype "input"))
    )
    (net (code "66") (name "Net-(IC13A-4Q)") (class "Default")
      (node (ref "IC13") (pin "9") (pinfunction "4Q_9") (pintype "tri_state"))
      (node (ref "IC8") (pin "8") (pinfunction "A4_8") (pintype "input"))
    )
    (net (code "67") (name "Net-(IC13A-5Q)") (class "Default")
      (node (ref "IC13") (pin "12") (pinfunction "5Q_12") (pintype "tri_state"))
      (node (ref "IC9") (pin "8") (pinfunction "A4_8") (pintype "input"))
    )
    (net (code "68") (name "Net-(IC13A-6Q)") (class "Default")
      (node (ref "IC13") (pin "15") (pinfunction "6Q_15") (pintype "tri_state"))
      (node (ref "IC9") (pin "6") (pinfunction "A3_6") (pintype "input"))
    )
    (net (code "69") (name "Net-(IC13A-7Q)") (class "Default")
      (node (ref "IC13") (pin "16") (pinfunction "7Q_16") (pintype "tri_state"))
      (node (ref "IC9") (pin "4") (pinfunction "A2_4") (pintype "input"))
    )
    (net (code "70") (name "Net-(IC13A-8Q)") (class "Default")
      (node (ref "IC13") (pin "19") (pinfunction "8Q_19") (pintype "tri_state"))
      (node (ref "IC9") (pin "2") (pinfunction "A1_2") (pintype "input"))
    )
    (net (code "71") (name "Net-(IC13A-ENC)") (class "Default")
      (node (ref "IC13") (pin "11") (pinfunction "ENC_11") (pintype "input"))
      (node (ref "IC15") (pin "10") (pinfunction "O_10") (pintype "output"))
    )
    (net (code "72") (name "Net-(IC15B-O)") (class "Default")
      (node (ref "IC15") (pin "4") (pinfunction "O_4") (pintype "output"))
      (node (ref "IC7") (pin "22") (pinfunction "~{CE}_22") (pintype "tri_state"))
    )
    (net (code "73") (name "Net-(IC15C-I0)") (class "Default")
      (node (ref "IC15") (pin "8") (pinfunction "I0_8") (pintype "input"))
      (node (ref "IC15") (pin "9") (pinfunction "I1_9") (pintype "input"))
      (node (ref "IC3") (pin "11") (pinfunction "O_11") (pintype "output"))
    )
    (net (code "74") (name "Net-(IC15D-O)") (class "Default")
      (node (ref "IC15") (pin "13") (pinfunction "O_13") (pintype "output"))
      (node (ref "IC3") (pin "12") (pinfunction "I0_12") (pintype "input"))
    )
    (net (code "75") (name "Net-(IC16B-I0)") (class "Default")
      (node (ref "IC16") (pin "4") (pinfunction "I0_4") (pintype "input"))
      (node (ref "IC2") (pin "2") (pinfunction "D_2") (pintype "input"))
      (node (ref "IC2") (pin "8") (pinfunction "~{Q}_8") (pintype "output"))
    )
    (net (code "76") (name "Net-(IC16B-I1)") (class "Default")
      (node (ref "IC16") (pin "5") (pinfunction "I1_5") (pintype "input"))
      (node (ref "IC2") (pin "6") (pinfunction "~{Q}_6") (pintype "output"))
    )
    (net (code "77") (name "Net-(IC16C-O)") (class "Default")
      (node (ref "IC16") (pin "13") (pinfunction "I1_13") (pintype "input"))
      (node (ref "IC16") (pin "8") (pinfunction "O_8") (pintype "output"))
    )
    (net (code "78") (name "Net-(IC17A-CS)") (class "Default")
      (node (ref "IC17") (pin "35") (pinfunction "CS_35") (pintype "input"))
      (node (ref "IC18") (pin "6") (pinfunction "O_6") (pintype "output"))
    )
    (net (code "79") (name "Net-(IC17A-IP0)") (class "Default")
      (node (ref "IC17") (pin "7") (pinfunction "IP0_7") (pintype "input"))
      (node (ref "JP3") (pin "5") (pinfunction "5_5") (pintype "passive"))
    )
    (net (code "80") (name "Net-(IC17A-IP1)") (class "Default")
      (node (ref "IC17") (pin "4") (pinfunction "IP1_4") (pintype "input"))
      (node (ref "JP1") (pin "5") (pinfunction "5_5") (pintype "passive"))
    )
    (net (code "81") (name "Net-(IC17A-OP0)") (class "Default")
      (node (ref "IC17") (pin "29") (pinfunction "OP0_29") (pintype "output"))
      (node (ref "JP3") (pin "1") (pinfunction "1_1") (pintype "passive"))
    )
    (net (code "82") (name "Net-(IC17A-OP1)") (class "Default")
      (node (ref "IC17") (pin "12") (pinfunction "OP1_12") (pintype "output"))
      (node (ref "JP1") (pin "1") (pinfunction "1_1") (pintype "passive"))
    )
    (net (code "83") (name "Net-(IC17A-OP6)") (class "Default")
      (node (ref "IC17") (pin "26") (pinfunction "OP6_26") (pintype "output"))
      (node (ref "R2") (pin "1") (pinfunction "1_1") (pintype "passive"))
    )
    (net (code "84") (name "Net-(IC17A-OP7)") (class "Default")
      (node (ref "IC17") (pin "15") (pinfunction "OP7_15") (pintype "output"))
      (node (ref "R1") (pin "1") (pinfunction "1_1") (pintype "passive"))
    )
    (net (code "85") (name "Net-(IC17A-RXDA)") (class "Default")
      (node (ref "IC17") (pin "31") (pinfunction "RXDA_31") (pintype "input"))
      (node (ref "JP3") (pin "2") (pinfunction "2_2") (pintype "passive"))
    )
    (net (code "86") (name "Net-(IC17A-RXDB)") (class "Default")
      (node (ref "IC17") (pin "10") (pinfunction "RXDB_10") (pintype "output"))
      (node (ref "JP1") (pin "2") (pinfunction "2_2") (pintype "passive"))
    )
    (net (code "87") (name "Net-(IC17A-TXDA)") (class "Default")
      (node (ref "IC17") (pin "30") (pinfunction "TXDA_30") (pintype "output"))
      (node (ref "JP3") (pin "3") (pinfunction "3_3") (pintype "passive"))
    )
    (net (code "88") (name "Net-(IC17A-TXDB)") (class "Default")
      (node (ref "IC17") (pin "11") (pinfunction "TXDB_11") (pintype "bidirectional"))
      (node (ref "JP1") (pin "3") (pinfunction "3_3") (pintype "passive"))
    )
    (net (code "89") (name "Net-(IC18A-O)") (class "Default")
      (node (ref "IC18") (pin "3") (pinfunction "O_3") (pintype "output"))
      (node (ref "IC5") (pin "9") (pinfunction "CS2_9") (pintype "input"))
    )
    (net (code "90") (name "Net-(IC18C-I0)") (class "Default")
      (node (ref "IC18") (pin "9") (pinfunction "I0_9") (pintype "input"))
      (node (ref "IC3") (pin "3") (pinfunction "O_3") (pintype "output"))
    )
    (net (code "91") (name "Net-(IC18C-O)") (class "Default")
      (node (ref "IC18") (pin "8") (pinfunction "O_8") (pintype "output"))
      (node (ref "IC7") (pin "24") (pinfunction "~{OE}_24") (pintype "input"))
    )
    (net (code "92") (name "Net-(IC18D-I0)") (class "Default")
      (node (ref "IC18") (pin "12") (pinfunction "I0_12") (pintype "input"))
      (node (ref "IC3") (pin "8") (pinfunction "O_8") (pintype "output"))
    )
    (net (code "93") (name "Net-(IC18D-O)") (class "Default")
      (node (ref "IC18") (pin "11") (pinfunction "O_11") (pintype "output"))
      (node (ref "IC6") (pin "22") (pinfunction "~{OE}_22") (pintype "input"))
    )
    (net (code "94") (name "Net-(LED1-PadA)") (class "Default")
      (node (ref "LED1") (pin "A") (pinfunction "A_A") (pintype "passive"))
      (node (ref "R17") (pin "2") (pinfunction "2_2") (pintype "passive"))
    )
    (net (code "95") (name "Net-(LED2-C)") (class "Default")
      (node (ref "LED2") (pin "K") (pinfunction "C_K") (pintype "passive"))
      (node (ref "R1") (pin "2") (pinfunction "2_2") (pintype "passive"))
    )
    (net (code "96") (name "Net-(LED3-C)") (class "Default")
      (node (ref "LED3") (pin "K") (pinfunction "C_K") (pintype "passive"))
      (node (ref "R2") (pin "2") (pinfunction "2_2") (pintype "passive"))
    )
    (net (code "97") (name "Net-(LED4-C)") (class "Default")
      (node (ref "LED4") (pin "K") (pinfunction "C_K") (pintype "passive"))
      (node (ref "R3") (pin "2") (pinfunction "2_2") (pintype "passive"))
    )
    (net (code "98") (name "PDIAG") (class "Default")
      (node (ref "CON1") (pin "46") (pinfunction "/PDIAG_46") (pintype "bidirectional"))
      (node (ref "RN1") (pin "8") (pinfunction "8_8") (pintype "passive"))
    )
    (net (code "99") (name "RDN") (class "Default")
      (node (ref "CON1") (pin "34") (pinfunction "/IORD_34") (pintype "input"))
      (node (ref "IC16") (pin "3") (pinfunction "O_3") (pintype "output"))
      (node (ref "IC18") (pin "10") (pinfunction "I1_10") (pintype "input"))
    )
    (net (code "100") (name "RESET") (class "Default")
      (node (ref "C7") (pin "+") (pinfunction "+_+") (pintype "passive"))
      (node (ref "IC1") (pin "37") (pinfunction "RESET_37") (pintype "input"))
      (node (ref "IC11") (pin "10") (pinfunction "PRE_10") (pintype "input"))
      (node (ref "IC12") (pin "7") (pinfunction "RESET_7") (pintype "bidirectional"))
      (node (ref "IC17") (pin "34") (pinfunction "RESET_34") (pintype "input"))
      (node (ref "RN1") (pin "6") (pinfunction "6_6") (pintype "passive"))
      (node (ref "S1") (pin "1") (pinfunction "S_1") (pintype "passive"))
      (node (ref "S1") (pin "2") (pinfunction "S1_2") (pintype "passive"))
    )
    (net (code "101") (name "RW") (class "Default")
      (node (ref "IC1") (pin "32") (pinfunction "R/~{W}_32") (pintype "output"))
      (node (ref "IC12") (pin "8") (pinfunction "R/W_8") (pintype "bidirectional"))
      (node (ref "IC16") (pin "10") (pinfunction "I1_10") (pintype "input"))
      (node (ref "IC16") (pin "2") (pinfunction "I1_2") (pintype "input"))
      (node (ref "IC16") (pin "9") (pinfunction "I0_9") (pintype "input"))
      (node (ref "IC17") (pin "8") (pinfunction "R/~{W}_8") (pintype "input"))
      (node (ref "IC3") (pin "4") (pinfunction "I0_4") (pintype "input"))
      (node (ref "IC5") (pin "13") (pinfunction "R/~{W}_13") (pintype "input"))
    )
    (net (code "102") (name "SCLK") (class "Default")
      (node (ref "IC17") (pin "32") (pinfunction "X1/CLK_32") (pintype "input"))
      (node (ref "IC5") (pin "3") (pinfunction "RXCLK_3") (pintype "input"))
      (node (ref "IC5") (pin "4") (pinfunction "TXCLK_4") (pintype "input"))
      (node (ref "QG2") (pin "5") (pinfunction "OUT_5") (pintype "output"))
    )
    (net (code "103") (name "SEREN") (class "Default")
      (node (ref "IC10") (pin "10") (pinfunction "Y5_10") (pintype "output"))
      (node (ref "IC18") (pin "4") (pinfunction "I0_4") (pintype "input"))
    )
    (net (code "104") (name "WRN") (class "Default")
      (node (ref "CON1") (pin "35") (pinfunction "/IOWR_35") (pintype "input"))
      (node (ref "IC16") (pin "11") (pinfunction "O_11") (pintype "output"))
      (node (ref "IC7") (pin "29") (pinfunction "~{WE}_29") (pintype "tri_state"))
    )
    (net (code "105") (name "unconnected-(CON1A-D08-Pad47)") (class "Default")
      (node (ref "CON1") (pin "47") (pinfunction "D08_47") (pintype "bidirectional"))
    )
    (net (code "106") (name "unconnected-(CON1A-D09-Pad48)") (class "Default")
      (node (ref "CON1") (pin "48") (pinfunction "D09_48") (pintype "bidirectional"))
    )
    (net (code "107") (name "unconnected-(CON1A-D10-Pad49)") (class "Default")
      (node (ref "CON1") (pin "49") (pinfunction "D10_49") (pintype "bidirectional"))
    )
    (net (code "108") (name "unconnected-(CON1A-D11-Pad27)") (class "Default")
      (node (ref "CON1") (pin "27") (pinfunction "D11_27") (pintype "bidirectional"))
    )
    (net (code "109") (name "unconnected-(CON1A-D12-Pad28)") (class "Default")
      (node (ref "CON1") (pin "28") (pinfunction "D12_28") (pintype "bidirectional"))
    )
    (net (code "110") (name "unconnected-(CON1A-D13-Pad29)") (class "Default")
      (node (ref "CON1") (pin "29") (pinfunction "D13_29") (pintype "bidirectional"))
    )
    (net (code "111") (name "unconnected-(CON1A-D14-Pad30)") (class "Default")
      (node (ref "CON1") (pin "30") (pinfunction "D14_30") (pintype "bidirectional"))
    )
    (net (code "112") (name "unconnected-(CON1A-D15-Pad31)") (class "Default")
      (node (ref "CON1") (pin "31") (pinfunction "D15_31") (pintype "bidirectional"))
    )
    (net (code "113") (name "unconnected-(CON1A-INTRQ-Pad37)") (class "Default")
      (node (ref "CON1") (pin "37") (pinfunction "INTRQ_37") (pintype "output"))
    )
    (net (code "114") (name "unconnected-(CON1A-IORDY-Pad42)") (class "Default")
      (node (ref "CON1") (pin "42") (pinfunction "IORDY_42") (pintype "output"))
    )
    (net (code "115") (name "unconnected-(CON1A-{slash}CD1-Pad26)") (class "Default")
      (node (ref "CON1") (pin "26") (pinfunction "/CD1_26") (pintype "output"))
    )
    (net (code "116") (name "unconnected-(CON1A-{slash}CD2-Pad25)") (class "Default")
      (node (ref "CON1") (pin "25") (pinfunction "/CD2_25") (pintype "output"))
    )
    (net (code "117") (name "unconnected-(CON1A-{slash}INPACK-Pad43)") (class "Default")
      (node (ref "CON1") (pin "43") (pinfunction "/INPACK_43") (pintype "output"))
    )
    (net (code "118") (name "unconnected-(CON1A-{slash}IOCS16-Pad24)") (class "Default")
      (node (ref "CON1") (pin "24") (pinfunction "/IOCS16_24") (pintype "output"))
    )
    (net (code "119") (name "unconnected-(CON1A-{slash}RESET-Pad41)") (class "Default")
      (node (ref "CON1") (pin "41") (pinfunction "/RESET_41") (pintype "input"))
    )
    (net (code "120") (name "unconnected-(CON1A-{slash}VS1-Pad33)") (class "Default")
      (node (ref "CON1") (pin "33") (pinfunction "/VS1_33") (pintype "output"))
    )
    (net (code "121") (name "unconnected-(CON1A-{slash}VS2-Pad40)") (class "Default")
      (node (ref "CON1") (pin "40") (pinfunction "/VS2_40") (pintype "output"))
    )
    (net (code "122") (name "unconnected-(IC1A-BA-Pad6)") (class "Default")
      (node (ref "IC1") (pin "6") (pinfunction "BA_6") (pintype "output"))
    )
    (net (code "123") (name "unconnected-(IC1A-BS-Pad5)") (class "Default")
      (node (ref "IC1") (pin "5") (pinfunction "BS_5") (pintype "output"))
    )
    (net (code "124") (name "unconnected-(IC1A-LIC-Pad38)") (class "Default")
      (node (ref "IC1") (pin "38") (pinfunction "LIC_38") (pintype "output"))
    )
    (net (code "125") (name "unconnected-(IC1A-TSC-Pad39)") (class "Default")
      (node (ref "IC1") (pin "39") (pinfunction "TSC_39") (pintype "input"))
    )
    (net (code "126") (name "unconnected-(IC4A-Y0-Pad15)") (class "Default")
      (node (ref "IC4") (pin "15") (pinfunction "Y0_15") (pintype "output"))
    )
    (net (code "127") (name "unconnected-(IC4A-Y1-Pad14)") (class "Default")
      (node (ref "IC4") (pin "14") (pinfunction "Y1_14") (pintype "output"))
    )
    (net (code "128") (name "unconnected-(IC4A-Y2-Pad13)") (class "Default")
      (node (ref "IC4") (pin "13") (pinfunction "Y2_13") (pintype "output"))
    )
    (net (code "129") (name "unconnected-(IC4A-Y3-Pad12)") (class "Default")
      (node (ref "IC4") (pin "12") (pinfunction "Y3_12") (pintype "output"))
    )
    (net (code "130") (name "unconnected-(IC4A-Y4-Pad11)") (class "Default")
      (node (ref "IC4") (pin "11") (pinfunction "Y4_11") (pintype "output"))
    )
    (net (code "131") (name "unconnected-(IC4A-Y5-Pad10)") (class "Default")
      (node (ref "IC4") (pin "10") (pinfunction "Y5_10") (pintype "output"))
    )
    (net (code "132") (name "unconnected-(IC4A-Y7-Pad7)") (class "Default")
      (node (ref "IC4") (pin "7") (pinfunction "Y7_7") (pintype "output"))
    )
    (net (code "133") (name "unconnected-(IC10A-Y6-Pad9)") (class "Default")
      (node (ref "IC10") (pin "9") (pinfunction "Y6_9") (pintype "output"))
    )
    (net (code "134") (name "unconnected-(IC10A-Y7-Pad7)") (class "Default")
      (node (ref "IC10") (pin "7") (pinfunction "Y7_7") (pintype "output"))
    )
    (net (code "135") (name "unconnected-(IC11A-Q-Pad5)") (class "Default")
      (node (ref "IC11") (pin "5") (pinfunction "Q_5") (pintype "output"))
    )
    (net (code "136") (name "unconnected-(IC11A-~{Q}-Pad6)") (class "Default")
      (node (ref "IC11") (pin "6") (pinfunction "~{Q}_6") (pintype "output"))
    )
    (net (code "137") (name "unconnected-(IC11B-~{Q}-Pad8)") (class "Default")
      (node (ref "IC11") (pin "8") (pinfunction "~{Q}_8") (pintype "output"))
    )
    (net (code "138") (name "unconnected-(IC12-IQRPE-Pad1)") (class "Default")
      (node (ref "IC12") (pin "1") (pinfunction "IQRPE_1") (pintype "bidirectional"))
    )
    (net (code "139") (name "unconnected-(IC12-IRQR-Pad23)") (class "Default")
      (node (ref "IC12") (pin "23") (pinfunction "IRQR_23") (pintype "bidirectional"))
    )
    (net (code "140") (name "unconnected-(IC14A-Y0-Pad15)") (class "Default")
      (node (ref "IC14") (pin "15") (pinfunction "Y0_15") (pintype "output"))
    )
    (net (code "141") (name "unconnected-(IC14A-Y1-Pad14)") (class "Default")
      (node (ref "IC14") (pin "14") (pinfunction "Y1_14") (pintype "output"))
    )
    (net (code "142") (name "unconnected-(IC14A-Y2-Pad13)") (class "Default")
      (node (ref "IC14") (pin "13") (pinfunction "Y2_13") (pintype "output"))
    )
    (net (code "143") (name "unconnected-(IC14A-Y3-Pad12)") (class "Default")
      (node (ref "IC14") (pin "12") (pinfunction "Y3_12") (pintype "output"))
    )
    (net (code "144") (name "unconnected-(IC14A-Y4-Pad11)") (class "Default")
      (node (ref "IC14") (pin "11") (pinfunction "Y4_11") (pintype "output"))
    )
    (net (code "145") (name "unconnected-(IC14A-Y5-Pad10)") (class "Default")
      (node (ref "IC14") (pin "10") (pinfunction "Y5_10") (pintype "output"))
    )
    (net (code "146") (name "unconnected-(IC14A-Y6-Pad9)") (class "Default")
      (node (ref "IC14") (pin "9") (pinfunction "Y6_9") (pintype "output"))
    )
    (net (code "147") (name "unconnected-(IC17A-DTACK-Pad9)") (class "Default")
      (node (ref "IC17") (pin "9") (pinfunction "DTACK_9") (pintype "output"))
    )
    (net (code "148") (name "unconnected-(IC17A-IP2-Pad36)") (class "Default")
      (node (ref "IC17") (pin "36") (pinfunction "IP2_36") (pintype "input"))
    )
    (net (code "149") (name "unconnected-(IC17A-IP3-Pad2)") (class "Default")
      (node (ref "IC17") (pin "2") (pinfunction "IP3_2") (pintype "input"))
    )
    (net (code "150") (name "unconnected-(IC17A-IP4-Pad39)") (class "Default")
      (node (ref "IC17") (pin "39") (pinfunction "IP4_39") (pintype "input"))
    )
    (net (code "151") (name "unconnected-(IC17A-IP5-Pad38)") (class "Default")
      (node (ref "IC17") (pin "38") (pinfunction "IP5_38") (pintype "input"))
    )
    (net (code "152") (name "unconnected-(IC17A-IRQ-Pad21)") (class "Default")
      (node (ref "IC17") (pin "21") (pinfunction "IRQ_21") (pintype "output"))
    )
    (net (code "153") (name "unconnected-(IC17A-OP2-Pad28)") (class "Default")
      (node (ref "IC17") (pin "28") (pinfunction "OP2_28") (pintype "output"))
    )
    (net (code "154") (name "unconnected-(IC17A-OP3-Pad13)") (class "Default")
      (node (ref "IC17") (pin "13") (pinfunction "OP3_13") (pintype "output"))
    )
    (net (code "155") (name "unconnected-(IC17A-OP4-Pad27)") (class "Default")
      (node (ref "IC17") (pin "27") (pinfunction "OP4_27") (pintype "output"))
    )
    (net (code "156") (name "unconnected-(IC17A-OP5-Pad14)") (class "Default")
      (node (ref "IC17") (pin "14") (pinfunction "OP5_14") (pintype "output"))
    )
    (net (code "157") (name "unconnected-(IC17A-X2-Pad33)") (class "Default")
      (node (ref "IC17") (pin "33") (pinfunction "X2_33") (pintype "output"))
    )
    (net (code "158") (name "unconnected-(J1-Pad2)") (class "Default")
      (node (ref "J1") (pin "2") (pinfunction "2_2") (pintype "passive"))
    )
    (net (code "159") (name "unconnected-(JP1-Pad4)") (class "Default")
      (node (ref "JP1") (pin "4") (pinfunction "4_4") (pintype "passive"))
    )
    (net (code "160") (name "unconnected-(JP2-Pad4)") (class "Default")
      (node (ref "JP2") (pin "4") (pinfunction "4_4") (pintype "passive"))
    )
    (net (code "161") (name "unconnected-(JP3-Pad4)") (class "Default")
      (node (ref "JP3") (pin "4") (pinfunction "4_4") (pintype "passive"))
    )
    (net (code "162") (name "unconnected-(QG1-TS-Pad1)") (class "Default")
      (node (ref "QG1") (pin "1") (pinfunction "TS_1") (pintype "passive"))
    )
    (net (code "163") (name "unconnected-(QG2-TS-Pad1)") (class "Default")
      (node (ref "QG2") (pin "1") (pinfunction "TS_1") (pintype "passive"))
    )
  )
)
